# vusbtinyisp_smt_voltage_reg.net
KiCad netlist of a schematic drawn in EAGLE
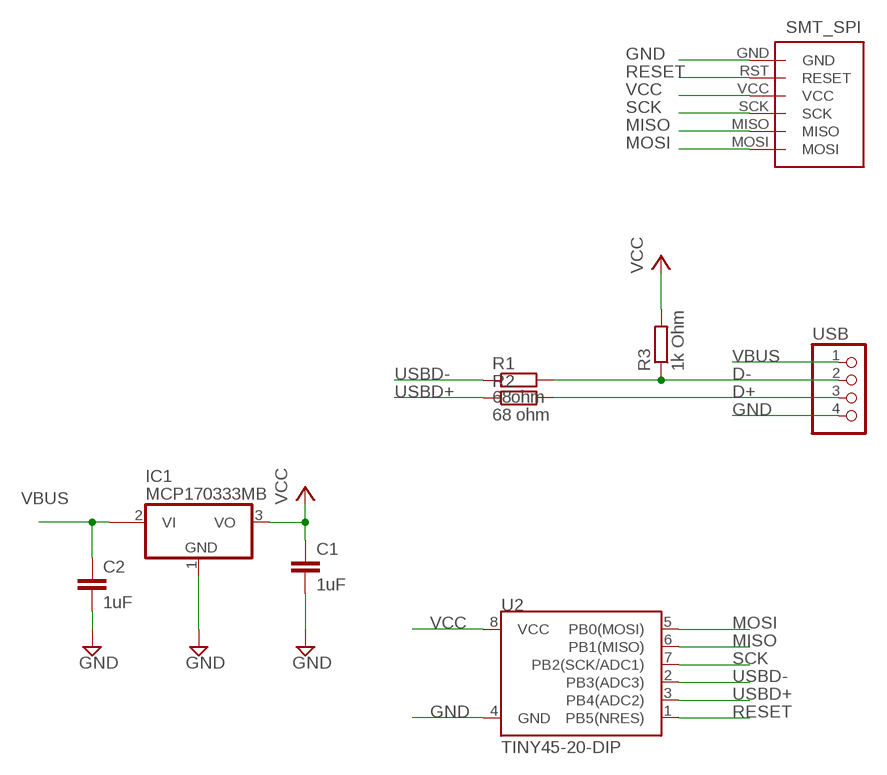
[diagram p0: schematic, sheet 1]

(export (version "E")
  (design (tool "Eeschema 10.0.6"))
  (components
    (comp (ref "C1")
      (value "1uF")
      (footprint "eagle-import:1206")
      (libsource (lib "eagle-import") (part "CAP1206"))
    )
    (comp (ref "C2")
      (value "1uF")
      (footprint "eagle-import:1206")
      (libsource (lib "eagle-import") (part "CAP1206"))
    )
    (comp (ref "IC1")
      (value "MCP170333MB")
      (footprint "eagle-import:SOT89")
      (libsource (lib "eagle-import") (part "MCP1703MB33"))
    )
    (comp (ref "R1")
      (value "68ohm")
      (footprint "eagle-import:R0805")
      (libsource (lib "eagle-import") (part "R-EU_R0805"))
    )
    (comp (ref "R2")
      (value "68 ohm")
      (footprint "eagle-import:R0805")
      (libsource (lib "eagle-import") (part "R-EU_R0805"))
    )
    (comp (ref "R3")
      (value "1k Ohm")
      (footprint "eagle-import:R1206")
      (libsource (lib "eagle-import") (part "R-EU_R1206"))
    )
    (comp (ref "U$1")
      (value "SMT_ISP")
      (footprint "eagle-import:SMT_PADS")
      (libsource (lib "eagle-import") (part "SMT_ISP"))
    )
    (comp (ref "U2")
      (value "TINY45-20-DIP")
      (footprint "eagle-import:DIP08")
      (libsource (lib "eagle-import") (part "ATTINY45TINY45-20-DIP"))
    )
    (comp (ref "USB")
      (value "PINHD-1X4")
      (footprint "eagle-import:1X04")
      (libsource (lib "eagle-import") (part "PINHD-1X4"))
    )
  )
  (nets
    (net (code "1") (name "/D+") (class "Default")
      (node (ref "R2") (pin "2") (pinfunction "2_2") (pintype "passive"))
      (node (ref "USB") (pin "3") (pinfunction "3_3") (pintype "passive"))
    )
    (net (code "2") (name "/D-") (class "Default")
      (node (ref "R1") (pin "2") (pinfunction "2_2") (pintype "passive"))
      (node (ref "R3") (pin "1") (pinfunction "1_1") (pintype "passive"))
      (node (ref "USB") (pin "2") (pinfunction "2_2") (pintype "passive"))
    )
    (net (code "3") (name "/MISO") (class "Default")
      (node (ref "U$1") (pin "MISO") (pinfunction "MISO_MISO") (pintype "bidirectional"))
      (node (ref "U2") (pin "6") (pinfunction "PB1(MISO)_6") (pintype "bidirectional"))
    )
    (net (code "4") (name "/MOSI") (class "Default")
      (node (ref "U$1") (pin "MOSI") (pinfunction "MOSI_MOSI") (pintype "bidirectional"))
      (node (ref "U2") (pin "5") (pinfunction "PB0(MOSI)_5") (pintype "bidirectional"))
    )
    (net (code "5") (name "/RESET") (class "Default")
      (node (ref "U$1") (pin "RST") (pinfunction "RESET_RST") (pintype "bidirectional"))
      (node (ref "U2") (pin "1") (pinfunction "PB5(NRES)_1") (pintype "bidirectional"))
    )
    (net (code "6") (name "/SCK") (class "Default")
      (node (ref "U$1") (pin "SCK") (pinfunction "SCK_SCK") (pintype "bidirectional"))
      (node (ref "U2") (pin "7") (pinfunction "PB2(SCK/ADC1)_7") (pintype "bidirectional"))
    )
    (net (code "7") (name "/USBD+") (class "Default")
      (node (ref "R2") (pin "1") (pinfunction "1_1") (pintype "passive"))
      (node (ref "U2") (pin "3") (pinfunction "PB4(ADC2)_3") (pintype "bidirectional"))
    )
    (net (code "8") (name "/USBD-") (class "Default")
      (node (ref "R1") (pin "1") (pinfunction "1_1") (pintype "passive"))
      (node (ref "U2") (pin "2") (pinfunction "PB3(ADC3)_2") (pintype "bidirectional"))
    )
    (net (code "9") (name "/VBUS") (class "Default")
      (node (ref "C2") (pin "1") (pinfunction "1_1") (pintype "passive"))
      (node (ref "IC1") (pin "2@1") (pinfunction "VI1_2@1") (pintype "input"))
      (node (ref "USB") (pin "1") (pinfunction "1_1") (pintype "passive"))
    )
    (net (code "10") (name "GND") (class "Default")
      (node (ref "C1") (pin "2") (pinfunction "2_2") (pintype "passive"))
      (node (ref "C2") (pin "2") (pinfunction "2_2") (pintype "passive"))
      (node (ref "IC1") (pin "1") (pinfunction "GND_1") (pintype "passive"))
      (node (ref "U$1") (pin "GND") (pinfunction "GND_GND") (pintype "bidirectional"))
      (node (ref "U2") (pin "4") (pinfunction "GND_4") (pintype "bidirectional"))
      (node (ref "USB") (pin "4") (pinfunction "4_4") (pintype "passive"))
    )
    (net (code "11") (name "VCC") (class "Default")
      (node (ref "C1") (pin "1") (pinfunction "1_1") (pintype "passive"))
      (node (ref "IC1") (pin "3") (pinfunction "VO_3") (pintype "passive"))
      (node (ref "R3") (pin "2") (pinfunction "2_2") (pintype "passive"))
      (node (ref "U$1") (pin "VCC") (pinfunction "VCC_VCC") (pintype "bidirectional"))
      (node (ref "U2") (pin "8") (pinfunction "VCC_8") (pintype "bidirectional"))
    )
    (net (code "12") (name "unconnected-(IC1-VI-Pad2)") (class "Default")
      (node (ref "IC1") (pin "2") (pinfunction "VI_2") (pintype "input"))
    )
  )
)
